# h_bridge_card.net
KiCad netlist of a schematic drawn in EAGLE
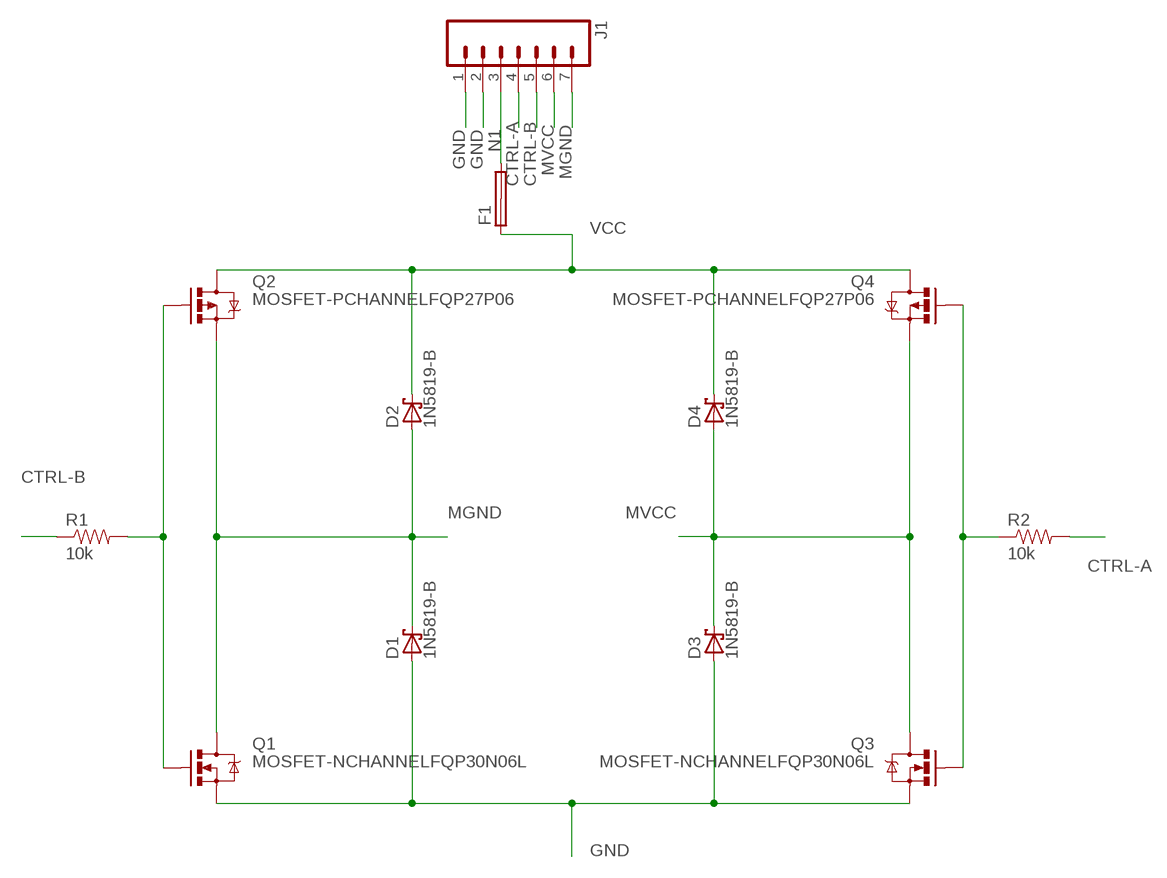
[diagram p0: schematic, sheet 1]

(export (version "E")
  (design (tool "Eeschema 10.0.6"))
  (components
    (comp (ref "D1")
      (value "1N5819-B")
      (footprint "eagle-import:DO41-7.6")
      (libsource (lib "eagle-import") (part "1N5819-B"))
    )
    (comp (ref "D2")
      (value "1N5819-B")
      (footprint "eagle-import:DO41-7.6")
      (libsource (lib "eagle-import") (part "1N5819-B"))
    )
    (comp (ref "D3")
      (value "1N5819-B")
      (footprint "eagle-import:DO41-7.6")
      (libsource (lib "eagle-import") (part "1N5819-B"))
    )
    (comp (ref "D4")
      (value "1N5819-B")
      (footprint "eagle-import:DO41-7.6")
      (libsource (lib "eagle-import") (part "1N5819-B"))
    )
    (comp (ref "F1")
      (value "SHK20L")
      (footprint "eagle-import:SHK20L")
      (libsource (lib "eagle-import") (part "SHK20L"))
    )
    (comp (ref "J1")
      (value "M07LOCK")
      (footprint "eagle-import:1X07_LOCK")
      (libsource (lib "eagle-import") (part "M07LOCK"))
    )
    (comp (ref "Q1")
      (value "MOSFET-NCHANNELFQP30N06L")
      (footprint "eagle-import:TO220V")
      (libsource (lib "eagle-import") (part "MOSFET-NCHANNELFQP30N06L"))
    )
    (comp (ref "Q2")
      (value "MOSFET-PCHANNELFQP27P06")
      (footprint "eagle-import:TO220V")
      (libsource (lib "eagle-import") (part "MOSFET-PCHANNELFQP27P06"))
    )
    (comp (ref "Q3")
      (value "MOSFET-NCHANNELFQP30N06L")
      (footprint "eagle-import:TO220V")
      (libsource (lib "eagle-import") (part "MOSFET-NCHANNELFQP30N06L"))
    )
    (comp (ref "Q4")
      (value "MOSFET-PCHANNELFQP27P06")
      (footprint "eagle-import:TO220V")
      (libsource (lib "eagle-import") (part "MOSFET-PCHANNELFQP27P06"))
    )
    (comp (ref "R1")
      (value "10k")
      (footprint "eagle-import:AXIAL-0.3")
      (libsource (lib "eagle-import") (part "10KOHM-1/4W5%(PTH)"))
    )
    (comp (ref "R2")
      (value "10k")
      (footprint "eagle-import:AXIAL-0.3")
      (libsource (lib "eagle-import") (part "10KOHM-1/4W5%(PTH)"))
    )
  )
  (nets
    (net (code "1") (name "/CTRL-A") (class "Default")
      (node (ref "J1") (pin "4") (pinfunction "4_4") (pintype "passive"))
      (node (ref "R2") (pin "P$2") (pinfunction "2_P$2") (pintype "passive"))
    )
    (net (code "2") (name "/CTRL-B") (class "Default")
      (node (ref "J1") (pin "5") (pinfunction "5_5") (pintype "passive"))
      (node (ref "R1") (pin "P$1") (pinfunction "1_P$1") (pintype "passive"))
    )
    (net (code "3") (name "/GND") (class "Default")
      (node (ref "D1") (pin "A") (pinfunction "A_A") (pintype "passive"))
      (node (ref "D3") (pin "A") (pinfunction "A_A") (pintype "passive"))
      (node (ref "J1") (pin "1") (pinfunction "1_1") (pintype "passive"))
      (node (ref "J1") (pin "2") (pinfunction "2_2") (pintype "passive"))
      (node (ref "Q1") (pin "3") (pinfunction "S_3") (pintype "passive"))
      (node (ref "Q3") (pin "3") (pinfunction "S_3") (pintype "passive"))
    )
    (net (code "4") (name "/MGND") (class "Default")
      (node (ref "D1") (pin "C") (pinfunction "C_C") (pintype "passive"))
      (node (ref "D2") (pin "A") (pinfunction "A_A") (pintype "passive"))
      (node (ref "J1") (pin "7") (pinfunction "7_7") (pintype "passive"))
      (node (ref "Q1") (pin "2") (pinfunction "D_2") (pintype "passive"))
      (node (ref "Q2") (pin "3") (pinfunction "S_3") (pintype "passive"))
    )
    (net (code "5") (name "/MVCC") (class "Default")
      (node (ref "D3") (pin "C") (pinfunction "C_C") (pintype "passive"))
      (node (ref "D4") (pin "A") (pinfunction "A_A") (pintype "passive"))
      (node (ref "J1") (pin "6") (pinfunction "6_6") (pintype "passive"))
      (node (ref "Q3") (pin "2") (pinfunction "D_2") (pintype "passive"))
      (node (ref "Q4") (pin "3") (pinfunction "S_3") (pintype "passive"))
    )
    (net (code "6") (name "/N1") (class "Default")
      (node (ref "F1") (pin "2A") (pinfunction "2A_2A") (pintype "passive"))
      (node (ref "J1") (pin "3") (pinfunction "3_3") (pintype "passive"))
    )
    (net (code "7") (name "/VCC") (class "Default")
      (node (ref "D2") (pin "C") (pinfunction "C_C") (pintype "passive"))
      (node (ref "D4") (pin "C") (pinfunction "C_C") (pintype "passive"))
      (node (ref "F1") (pin "1A") (pinfunction "1A_1A") (pintype "passive"))
      (node (ref "Q2") (pin "2") (pinfunction "D_2") (pintype "passive"))
      (node (ref "Q4") (pin "2") (pinfunction "D_2") (pintype "passive"))
    )
    (net (code "8") (name "Net-(Q1-G)") (class "Default")
      (node (ref "Q1") (pin "1") (pinfunction "G_1") (pintype "passive"))
      (node (ref "Q2") (pin "1") (pinfunction "G_1") (pintype "passive"))
      (node (ref "R1") (pin "P$2") (pinfunction "2_P$2") (pintype "passive"))
    )
    (net (code "9") (name "Net-(Q3-G)") (class "Default")
      (node (ref "Q3") (pin "1") (pinfunction "G_1") (pintype "passive"))
      (node (ref "Q4") (pin "1") (pinfunction "G_1") (pintype "passive"))
      (node (ref "R2") (pin "P$1") (pinfunction "1_P$1") (pintype "passive"))
    )
    (net (code "10") (name "unconnected-(F1-Pad1B)") (class "Default")
      (node (ref "F1") (pin "1B") (pinfunction "1B_1B") (pintype "passive"))
    )
    (net (code "11") (name "unconnected-(F1-Pad2B)") (class "Default")
      (node (ref "F1") (pin "2B") (pinfunction "2B_2B") (pintype "passive"))
    )
  )
)
